# recall_mcu_v0_1.net
KiCad netlist of a schematic drawn in Altium Designer
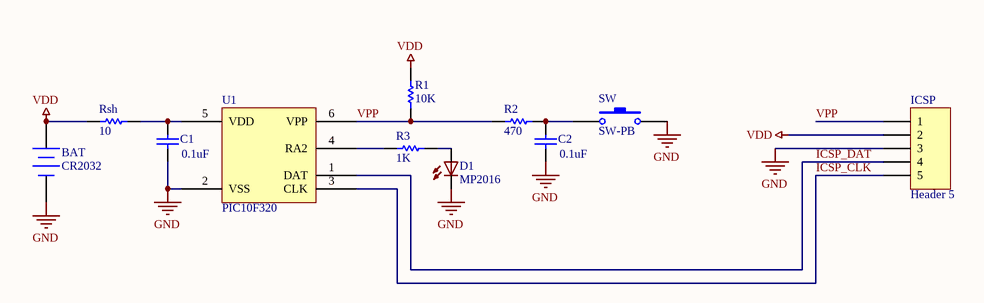
[diagram p0: recall_mcu_v0_1.SchDoc]

(export (version "E")
  (design (tool "Eeschema 10.0.6"))
  (components
    (comp (ref "BAT")
      (value "CR2032")
      (footprint "BAT-HLD-001-THM")
      (fields (field (name "PUBLISHER") "Altium Limited"))
      (libsource (lib "recall") (part "Battery"))
    )
    (comp (ref "C1")
      (value "0.1uF")
      (footprint "CAP_0402R")
      (description "Capacitor")
      (fields (field (name "Comment") "CAP") (field (name "PUBLISHER") "Altium Limited"))
      (libsource (lib "recall") (part "CAP"))
    )
    (comp (ref "C2")
      (value "0.1uF")
      (footprint "CAP_0402R")
      (description "Capacitor")
      (fields (field (name "Comment") "CAP") (field (name "PUBLISHER") "Altium Limited"))
      (libsource (lib "recall") (part "CAP"))
    )
    (comp (ref "D1")
      (value "MP2016")
      (footprint "MP2016")
      (description "MP2016 White LED")
      (libsource (lib "recall") (part "MP2016"))
    )
    (comp (ref "ICSP")
      (value "Header 5")
      (footprint "HDR1X5_ICSP")
      (description "Header, 5-Pin")
      (fields (field (name "PUBLISHER") "Altium Limited"))
      (libsource (lib "recall") (part "Header 5"))
    )
    (comp (ref "R1")
      (value "10K")
      (footprint "RES_0402")
      (description "Resistor")
      (fields (field (name "Comment") "RES") (field (name "PUBLISHER") "Altium Limited"))
      (libsource (lib "recall") (part "RES"))
    )
    (comp (ref "R2")
      (value "470")
      (footprint "RES_0402")
      (description "Resistor")
      (fields (field (name "Comment") "RES") (field (name "PUBLISHER") "Altium Limited"))
      (libsource (lib "recall") (part "RES"))
    )
    (comp (ref "R3")
      (value "1K")
      (footprint "RES_0402")
      (description "Resistor")
      (fields (field (name "Comment") "RES") (field (name "PUBLISHER") "Altium Limited"))
      (libsource (lib "recall") (part "RES"))
    )
    (comp (ref "Rsh")
      (value "10")
      (footprint "RES_0402")
      (description "Resistor")
      (fields (field (name "Comment") "RES") (field (name "PUBLISHER") "Altium Limited"))
      (libsource (lib "recall") (part "RES"))
    )
    (comp (ref "SW")
      (value "SW-PB")
      (footprint "TRELLIS_1x1")
      (description "Translucent Conductive Silicone Elastomer Switch")
      (fields (field (name "PUBLISHER") "Altium Limited"))
      (libsource (lib "recall") (part "SW-PB"))
    )
    (comp (ref "U1")
      (value "PIC10F320")
      (footprint "SOT-23-6")
      (description "6-Pin Flash-Based, 8-Bit Microcontroller")
      (libsource (lib "recall") (part "PIC10F320"))
    )
  )
  (nets
    (net (code "1") (name "/ICSP_CLK") (class "Default")
      (node (ref "ICSP") (pin "5") (pinfunction "5_5") (pintype "passive"))
      (node (ref "U1") (pin "3") (pinfunction "CLK_3") (pintype "passive"))
    )
    (net (code "2") (name "/ICSP_DAT") (class "Default")
      (node (ref "ICSP") (pin "4") (pinfunction "4_4") (pintype "passive"))
      (node (ref "U1") (pin "1") (pinfunction "DAT_1") (pintype "passive"))
    )
    (net (code "3") (name "/VPP") (class "Default")
      (node (ref "ICSP") (pin "1") (pinfunction "1_1") (pintype "passive"))
      (node (ref "R1") (pin "1") (pinfunction "1_1") (pintype "passive"))
      (node (ref "R2") (pin "2") (pinfunction "2_2") (pintype "passive"))
      (node (ref "U1") (pin "6") (pinfunction "VPP_6") (pintype "passive"))
    )
    (net (code "4") (name "GND") (class "Default")
      (node (ref "BAT") (pin "2") (pinfunction "-_2") (pintype "passive"))
      (node (ref "C1") (pin "1") (pinfunction "1_1") (pintype "passive"))
      (node (ref "C2") (pin "1") (pinfunction "1_1") (pintype "passive"))
      (node (ref "D1") (pin "C") (pinfunction "C_C") (pintype "passive"))
      (node (ref "ICSP") (pin "3") (pinfunction "3_3") (pintype "passive"))
      (node (ref "SW") (pin "2") (pinfunction "2_2") (pintype "passive"))
      (node (ref "U1") (pin "2") (pinfunction "VSS_2") (pintype "passive"))
    )
    (net (code "5") (name "Net-(C2-Pad2)") (class "Default")
      (node (ref "C2") (pin "2") (pinfunction "2_2") (pintype "passive"))
      (node (ref "R2") (pin "1") (pinfunction "1_1") (pintype "passive"))
      (node (ref "SW") (pin "1") (pinfunction "1_1") (pintype "passive"))
    )
    (net (code "6") (name "Net-(D1-PadA)") (class "Default")
      (node (ref "D1") (pin "A") (pinfunction "A_A") (pintype "passive"))
      (node (ref "R3") (pin "1") (pinfunction "1_1") (pintype "passive"))
    )
    (net (code "7") (name "Net-(U1-RA2)") (class "Default")
      (node (ref "R3") (pin "2") (pinfunction "2_2") (pintype "passive"))
      (node (ref "U1") (pin "4") (pinfunction "RA2_4") (pintype "passive"))
    )
    (net (code "8") (name "Net-(U1-VDD)") (class "Default")
      (node (ref "C1") (pin "2") (pinfunction "2_2") (pintype "passive"))
      (node (ref "Rsh") (pin "2") (pinfunction "2_2") (pintype "passive"))
      (node (ref "U1") (pin "5") (pinfunction "VDD_5") (pintype "passive"))
    )
    (net (code "9") (name "VDD") (class "Default")
      (node (ref "BAT") (pin "1") (pinfunction "+_1") (pintype "passive"))
      (node (ref "ICSP") (pin "2") (pinfunction "2_2") (pintype "passive"))
      (node (ref "R1") (pin "2") (pinfunction "2_2") (pintype "passive"))
      (node (ref "Rsh") (pin "1") (pinfunction "1_1") (pintype "passive"))
    )
  )
)
